# EC_Sensor.net
KiCad netlist of a schematic drawn in EAGLE
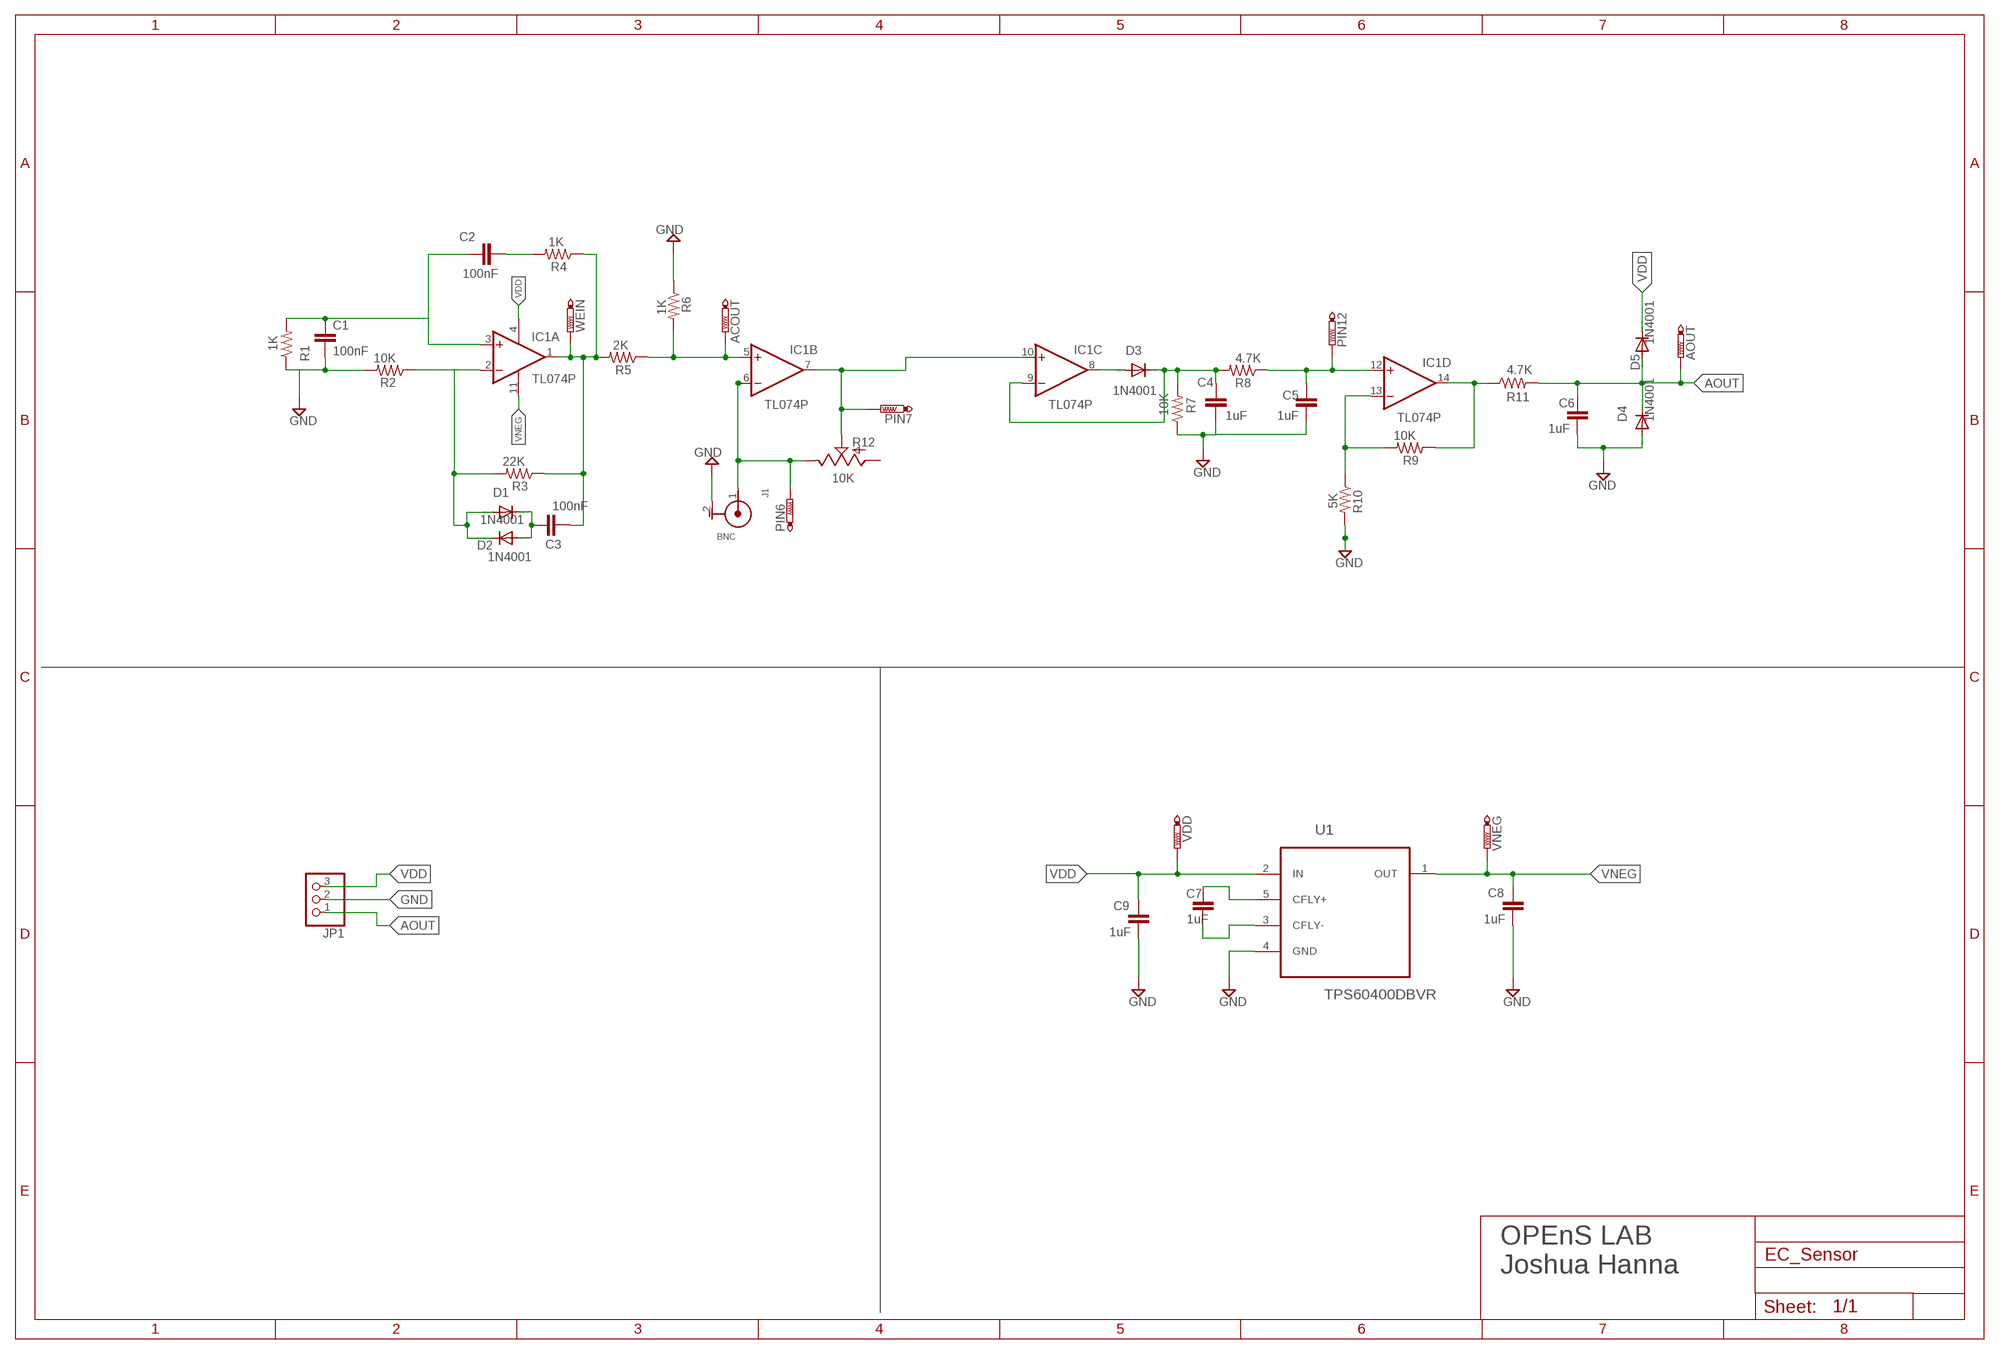
[diagram p0: schematic, sheet 1]

(export (version "E")
  (design (tool "Eeschema 10.0.6"))
  (components
    (comp (ref "ACOUT")
      (value "PTR1PAD1-13")
      (footprint "eagle-import:P1-13")
      (libsource (lib "eagle-import") (part "PTR1PAD1-13"))
    )
    (comp (ref "AOUT")
      (value "PTR1PAD1-13")
      (footprint "eagle-import:P1-13")
      (libsource (lib "eagle-import") (part "PTR1PAD1-13"))
    )
    (comp (ref "C1")
      (value "100nF")
      (footprint "eagle-import:C1206")
      (libsource (lib "eagle-import") (part "C-EUC1206"))
    )
    (comp (ref "C2")
      (value "100nF")
      (footprint "eagle-import:C1206")
      (libsource (lib "eagle-import") (part "C-EUC1206"))
    )
    (comp (ref "C3")
      (value "100nF")
      (footprint "eagle-import:C1206")
      (libsource (lib "eagle-import") (part "C-EUC1206"))
    )
    (comp (ref "C4")
      (value "1uF")
      (footprint "eagle-import:C1206")
      (libsource (lib "eagle-import") (part "C-EUC1206"))
    )
    (comp (ref "C5")
      (value "1uF")
      (footprint "eagle-import:C1206")
      (libsource (lib "eagle-import") (part "C-EUC1206"))
    )
    (comp (ref "C6")
      (value "1uF")
      (footprint "eagle-import:C1206")
      (libsource (lib "eagle-import") (part "C-EUC1206"))
    )
    (comp (ref "C7")
      (value "1uF")
      (footprint "eagle-import:C1206")
      (libsource (lib "eagle-import") (part "C-EUC1206"))
    )
    (comp (ref "C8")
      (value "1uF")
      (footprint "eagle-import:C1206")
      (libsource (lib "eagle-import") (part "C-EUC1206"))
    )
    (comp (ref "C9")
      (value "1uF")
      (footprint "eagle-import:C1206")
      (libsource (lib "eagle-import") (part "C-EUC1206"))
    )
    (comp (ref "D1")
      (value "1N4001")
      (footprint "eagle-import:D-5")
      (libsource (lib "eagle-import") (part "DIODE-D-5"))
    )
    (comp (ref "D2")
      (value "1N4001")
      (footprint "eagle-import:D-5")
      (libsource (lib "eagle-import") (part "DIODE-D-5"))
    )
    (comp (ref "D3")
      (value "1N4001")
      (footprint "eagle-import:D-5")
      (libsource (lib "eagle-import") (part "DIODE-D-5"))
    )
    (comp (ref "D4")
      (value "1N4001")
      (footprint "eagle-import:D-5")
      (libsource (lib "eagle-import") (part "DIODE-D-5"))
    )
    (comp (ref "D5")
      (value "1N4001")
      (footprint "eagle-import:D-5")
      (libsource (lib "eagle-import") (part "DIODE-D-5"))
    )
    (comp (ref "IC1")
      (value "TL074P")
      (footprint "eagle-import:DIL14")
      (libsource (lib "eagle-import") (part "TL074P"))
    )
    (comp (ref "J1")
      (value "BNC")
      (footprint "eagle-import:TE_227161-1")
      (fields (field (name "COMMENT") "227161-1") (field (name "MF") "TE Connectivity"))
      (libsource (lib "eagle-import") (part "227161-1"))
    )
    (comp (ref "JP1")
      (value "PINHD-1X3")
      (footprint "eagle-import:1X03")
      (libsource (lib "eagle-import") (part "PINHD-1X3"))
    )
    (comp (ref "PIN6")
      (value "PTR1PAD1-13")
      (footprint "eagle-import:P1-13")
      (libsource (lib "eagle-import") (part "PTR1PAD1-13"))
    )
    (comp (ref "PIN7")
      (value "PTR1PAD1-13")
      (footprint "eagle-import:P1-13")
      (libsource (lib "eagle-import") (part "PTR1PAD1-13"))
    )
    (comp (ref "PIN12")
      (value "PTR1PAD1-13")
      (footprint "eagle-import:P1-13")
      (libsource (lib "eagle-import") (part "PTR1PAD1-13"))
    )
    (comp (ref "R1")
      (value "1K")
      (footprint "eagle-import:R1206")
      (libsource (lib "eagle-import") (part "R-US_R1206"))
    )
    (comp (ref "R2")
      (value "10K")
      (footprint "eagle-import:R1206")
      (libsource (lib "eagle-import") (part "R-US_R1206"))
    )
    (comp (ref "R3")
      (value "22K")
      (footprint "eagle-import:R1206")
      (libsource (lib "eagle-import") (part "R-US_R1206"))
    )
    (comp (ref "R4")
      (value "1K")
      (footprint "eagle-import:R1206")
      (libsource (lib "eagle-import") (part "R-US_R1206"))
    )
    (comp (ref "R5")
      (value "2K")
      (footprint "eagle-import:R1206")
      (libsource (lib "eagle-import") (part "R-US_R1206"))
    )
    (comp (ref "R6")
      (value "1K")
      (footprint "eagle-import:R1206")
      (libsource (lib "eagle-import") (part "R-US_R1206"))
    )
    (comp (ref "R7")
      (value "10K")
      (footprint "eagle-import:R1206")
      (libsource (lib "eagle-import") (part "R-US_R1206"))
    )
    (comp (ref "R8")
      (value "4.7K")
      (footprint "eagle-import:R1206")
      (libsource (lib "eagle-import") (part "R-US_R1206"))
    )
    (comp (ref "R9")
      (value "10K")
      (footprint "eagle-import:R1206")
      (libsource (lib "eagle-import") (part "R-US_R1206"))
    )
    (comp (ref "R10")
      (value "5K")
      (footprint "eagle-import:R1206")
      (libsource (lib "eagle-import") (part "R-US_R1206"))
    )
    (comp (ref "R11")
      (value "4.7K")
      (footprint "eagle-import:R1206")
      (libsource (lib "eagle-import") (part "R-US_R1206"))
    )
    (comp (ref "R12")
      (value "10K")
      (footprint "eagle-import:B64Y")
      (libsource (lib "eagle-import") (part "TRIM_US-B64Y"))
    )
    (comp (ref "U1")
      (value "TPS60400DBVR")
      (footprint "eagle-import:SOT95P280X145-5N")
      (fields (field (name "MF") "Texas Instruments"))
      (libsource (lib "eagle-import") (part "TPS60400DBVR"))
    )
    (comp (ref "VDD")
      (value "PTR1PAD1-13")
      (footprint "eagle-import:P1-13")
      (libsource (lib "eagle-import") (part "PTR1PAD1-13"))
    )
    (comp (ref "VNEG")
      (value "PTR1PAD1-13")
      (footprint "eagle-import:P1-13")
      (libsource (lib "eagle-import") (part "PTR1PAD1-13"))
    )
    (comp (ref "WEIN")
      (value "PTR1PAD1-13")
      (footprint "eagle-import:P1-13")
      (libsource (lib "eagle-import") (part "PTR1PAD1-13"))
    )
  )
  (nets
    (net (code "1") (name "AOUT") (class "Default")
      (node (ref "AOUT") (pin "TP") (pinfunction "TP_TP") (pintype "input"))
      (node (ref "C6") (pin "2") (pinfunction "2_2") (pintype "passive"))
      (node (ref "D4") (pin "C") (pinfunction "C_C") (pintype "passive"))
      (node (ref "D5") (pin "A") (pinfunction "A_A") (pintype "passive"))
      (node (ref "JP1") (pin "1") (pinfunction "1_1") (pintype "passive"))
      (node (ref "R11") (pin "2") (pinfunction "2_2") (pintype "passive"))
    )
    (net (code "2") (name "GND") (class "Default")
      (node (ref "C1") (pin "2") (pinfunction "2_2") (pintype "passive"))
      (node (ref "C4") (pin "1") (pinfunction "1_1") (pintype "passive"))
      (node (ref "C5") (pin "1") (pinfunction "1_1") (pintype "passive"))
      (node (ref "C6") (pin "1") (pinfunction "1_1") (pintype "passive"))
      (node (ref "C8") (pin "1") (pinfunction "1_1") (pintype "passive"))
      (node (ref "C9") (pin "1") (pinfunction "1_1") (pintype "passive"))
      (node (ref "D4") (pin "A") (pinfunction "A_A") (pintype "passive"))
      (node (ref "J1") (pin "2") (pinfunction "G_2") (pintype "power_in"))
      (node (ref "JP1") (pin "2") (pinfunction "2_2") (pintype "passive"))
      (node (ref "R1") (pin "1") (pinfunction "1_1") (pintype "passive"))
      (node (ref "R10") (pin "2") (pinfunction "2_2") (pintype "passive"))
      (node (ref "R2") (pin "2") (pinfunction "2_2") (pintype "passive"))
      (node (ref "R6") (pin "1") (pinfunction "1_1") (pintype "passive"))
      (node (ref "R7") (pin "1") (pinfunction "1_1") (pintype "passive"))
      (node (ref "U1") (pin "4") (pinfunction "GND_4") (pintype "passive"))
    )
    (net (code "3") (name "Net-(C2-Pad2)") (class "Default")
      (node (ref "C2") (pin "2") (pinfunction "2_2") (pintype "passive"))
      (node (ref "R4") (pin "2") (pinfunction "2_2") (pintype "passive"))
    )
    (net (code "4") (name "Net-(C3-Pad1)") (class "Default")
      (node (ref "C3") (pin "1") (pinfunction "1_1") (pintype "passive"))
      (node (ref "D1") (pin "C") (pinfunction "C_C") (pintype "passive"))
      (node (ref "D2") (pin "A") (pinfunction "A_A") (pintype "passive"))
    )
    (net (code "5") (name "Net-(IC1A-+IN)") (class "Default")
      (node (ref "C1") (pin "1") (pinfunction "1_1") (pintype "passive"))
      (node (ref "C2") (pin "1") (pinfunction "1_1") (pintype "passive"))
      (node (ref "IC1") (pin "3") (pinfunction "+IN_3") (pintype "input"))
      (node (ref "R1") (pin "2") (pinfunction "2_2") (pintype "passive"))
    )
    (net (code "6") (name "Net-(IC1A--IN)") (class "Default")
      (node (ref "D1") (pin "A") (pinfunction "A_A") (pintype "passive"))
      (node (ref "D2") (pin "C") (pinfunction "C_C") (pintype "passive"))
      (node (ref "IC1") (pin "2") (pinfunction "-IN_2") (pintype "input"))
      (node (ref "R2") (pin "1") (pinfunction "1_1") (pintype "passive"))
      (node (ref "R3") (pin "2") (pinfunction "2_2") (pintype "passive"))
    )
    (net (code "7") (name "Net-(IC1A-OUT)") (class "Default")
      (node (ref "C3") (pin "2") (pinfunction "2_2") (pintype "passive"))
      (node (ref "IC1") (pin "1") (pinfunction "OUT_1") (pintype "output"))
      (node (ref "R3") (pin "1") (pinfunction "1_1") (pintype "passive"))
      (node (ref "R4") (pin "1") (pinfunction "1_1") (pintype "passive"))
      (node (ref "R5") (pin "2") (pinfunction "2_2") (pintype "passive"))
      (node (ref "WEIN") (pin "TP") (pinfunction "TP_TP") (pintype "input"))
    )
    (net (code "8") (name "Net-(IC1B-+IN)") (class "Default")
      (node (ref "ACOUT") (pin "TP") (pinfunction "TP_TP") (pintype "input"))
      (node (ref "IC1") (pin "5") (pinfunction "+IN_5") (pintype "input"))
      (node (ref "R5") (pin "1") (pinfunction "1_1") (pintype "passive"))
      (node (ref "R6") (pin "2") (pinfunction "2_2") (pintype "passive"))
    )
    (net (code "9") (name "Net-(IC1B--IN)") (class "Default")
      (node (ref "IC1") (pin "6") (pinfunction "-IN_6") (pintype "input"))
      (node (ref "J1") (pin "1") (pinfunction "C_1") (pintype "passive"))
      (node (ref "PIN6") (pin "TP") (pinfunction "TP_TP") (pintype "input"))
      (node (ref "R12") (pin "E") (pinfunction "E_E") (pintype "passive"))
    )
    (net (code "10") (name "Net-(IC1B-OUT)") (class "Default")
      (node (ref "IC1") (pin "10") (pinfunction "+IN_10") (pintype "input"))
      (node (ref "IC1") (pin "7") (pinfunction "OUT_7") (pintype "output"))
      (node (ref "PIN7") (pin "TP") (pinfunction "TP_TP") (pintype "input"))
      (node (ref "R12") (pin "S") (pinfunction "S_S") (pintype "passive"))
    )
    (net (code "11") (name "Net-(IC1C--IN)") (class "Default")
      (node (ref "C4") (pin "2") (pinfunction "2_2") (pintype "passive"))
      (node (ref "D3") (pin "C") (pinfunction "C_C") (pintype "passive"))
      (node (ref "IC1") (pin "9") (pinfunction "-IN_9") (pintype "input"))
      (node (ref "R7") (pin "2") (pinfunction "2_2") (pintype "passive"))
      (node (ref "R8") (pin "2") (pinfunction "2_2") (pintype "passive"))
    )
    (net (code "12") (name "Net-(IC1C-OUT)") (class "Default")
      (node (ref "D3") (pin "A") (pinfunction "A_A") (pintype "passive"))
      (node (ref "IC1") (pin "8") (pinfunction "OUT_8") (pintype "output"))
    )
    (net (code "13") (name "Net-(IC1D-+IN)") (class "Default")
      (node (ref "C5") (pin "2") (pinfunction "2_2") (pintype "passive"))
      (node (ref "IC1") (pin "12") (pinfunction "+IN_12") (pintype "input"))
      (node (ref "PIN12") (pin "TP") (pinfunction "TP_TP") (pintype "input"))
      (node (ref "R8") (pin "1") (pinfunction "1_1") (pintype "passive"))
    )
    (net (code "14") (name "Net-(IC1D--IN)") (class "Default")
      (node (ref "IC1") (pin "13") (pinfunction "-IN_13") (pintype "input"))
      (node (ref "R10") (pin "1") (pinfunction "1_1") (pintype "passive"))
      (node (ref "R9") (pin "2") (pinfunction "2_2") (pintype "passive"))
    )
    (net (code "15") (name "Net-(IC1D-OUT)") (class "Default")
      (node (ref "IC1") (pin "14") (pinfunction "OUT_14") (pintype "output"))
      (node (ref "R11") (pin "1") (pinfunction "1_1") (pintype "passive"))
      (node (ref "R9") (pin "1") (pinfunction "1_1") (pintype "passive"))
    )
    (net (code "16") (name "Net-(U1-CFLY+)") (class "Default")
      (node (ref "C7") (pin "2") (pinfunction "2_2") (pintype "passive"))
      (node (ref "U1") (pin "5") (pinfunction "CFLY+_5") (pintype "input"))
    )
    (net (code "17") (name "Net-(U1-CFLY-)") (class "Default")
      (node (ref "C7") (pin "1") (pinfunction "1_1") (pintype "passive"))
      (node (ref "U1") (pin "3") (pinfunction "CFLY-_3") (pintype "input"))
    )
    (net (code "18") (name "VDD") (class "Default")
      (node (ref "C9") (pin "2") (pinfunction "2_2") (pintype "passive"))
      (node (ref "D5") (pin "C") (pinfunction "C_C") (pintype "passive"))
      (node (ref "IC1") (pin "4") (pinfunction "V+_4") (pintype "power_in"))
      (node (ref "JP1") (pin "3") (pinfunction "3_3") (pintype "passive"))
      (node (ref "U1") (pin "2") (pinfunction "IN_2") (pintype "power_in"))
      (node (ref "VDD") (pin "TP") (pinfunction "TP_TP") (pintype "input"))
    )
    (net (code "19") (name "VNEG") (class "Default")
      (node (ref "C8") (pin "2") (pinfunction "2_2") (pintype "passive"))
      (node (ref "IC1") (pin "11") (pinfunction "V-_11") (pintype "power_in"))
      (node (ref "U1") (pin "1") (pinfunction "OUT_1") (pintype "output"))
      (node (ref "VNEG") (pin "TP") (pinfunction "TP_TP") (pintype "input"))
    )
    (net (code "20") (name "unconnected-(R12-PadA)") (class "Default")
      (node (ref "R12") (pin "A") (pinfunction "A_A") (pintype "passive"))
    )
  )
)
